# ZeroCrossingDetector.net
KiCad netlist of a schematic drawn in Altium Designer
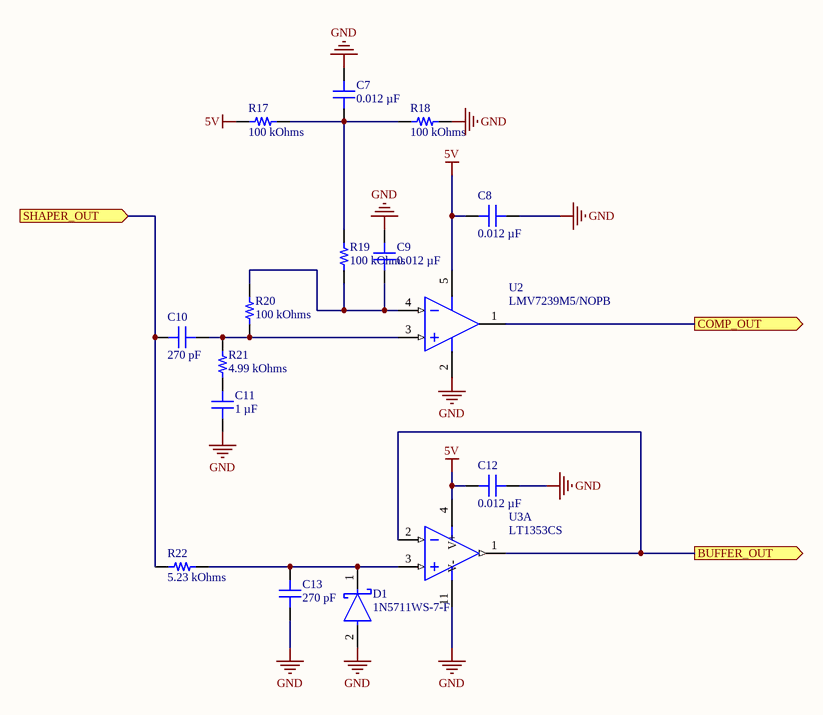
[diagram p0: ZeroCrossingDetector.SchDoc]

(export (version "E")
  (design (tool "Eeschema 10.0.6"))
  (components
    (comp (ref "C7")
      (value "0.012 µF")
      (footprint "CAP 0603_1608")
      (description "CAP CER 0.012UF 16V X7R 0603")
      (fields (field (name "PART NUMBER") "CC0603KRX7R7BB123") (field (name "MANUFACTURER") "Yageo"))
      (libsource (lib "CAL") (part "Capacitor"))
    )
    (comp (ref "C8")
      (value "0.012 µF")
      (footprint "CAP 0603_1608")
      (description "CAP CER 0.012UF 16V X7R 0603")
      (fields (field (name "PART NUMBER") "CC0603KRX7R7BB123") (field (name "MANUFACTURER") "Yageo"))
      (libsource (lib "CAL") (part "Capacitor"))
    )
    (comp (ref "C9")
      (value "0.012 µF")
      (footprint "CAP 0603_1608")
      (description "CAP CER 0.012UF 16V X7R 0603")
      (fields (field (name "PART NUMBER") "CC0603KRX7R7BB123") (field (name "MANUFACTURER") "Yageo"))
      (libsource (lib "CAL") (part "Capacitor"))
    )
    (comp (ref "C10")
      (value "270 pF")
      (footprint "CAP 0603_1608")
      (description "CAP CER 270 PF 16V C0G 0603")
      (fields
        (field (name "PART NUMBER") "VJ0603D271JXJQJHT")
        (field (name "MANUFACTURER") "Vishay Vitramon")
      )
      (libsource (lib "CAL") (part "Capacitor"))
    )
    (comp (ref "C11")
      (value "1 µF")
      (footprint "CAP 0603_1608")
      (description "CAP CER 1UF 16V X5R 0603")
      (fields (field (name "PART NUMBER") "CC0603KRX5R7BB105") (field (name "MANUFACTURER") "Yageo"))
      (libsource (lib "CAL") (part "Capacitor"))
    )
    (comp (ref "C12")
      (value "0.012 µF")
      (footprint "CAP 0603_1608")
      (description "CAP CER 0.012UF 16V X7R 0603")
      (fields (field (name "PART NUMBER") "CC0603KRX7R7BB123") (field (name "MANUFACTURER") "Yageo"))
      (libsource (lib "CAL") (part "Capacitor"))
    )
    (comp (ref "C13")
      (value "270 pF")
      (footprint "CAP 0603_1608")
      (description "CAP CER 270 PF 16V C0G 0603")
      (fields
        (field (name "PART NUMBER") "VJ0603D271JXJQJHT")
        (field (name "MANUFACTURER") "Vishay Vitramon")
      )
      (libsource (lib "CAL") (part "Capacitor"))
    )
    (comp (ref "D1")
      (value "1N5711WS-7-F")
      (footprint "FP-SOD323-MFG")
      (description "DIODE SCHOTTKY 70V 150MW SOD323")
      (fields
        (field (name "OCTOPART") "https://octopart.com/1n5711ws-7-f-diodes+inc.-323167")
        (field (name "MANUFACTURER") "Diodes Inc")
      )
      (libsource (lib "Altium Content Vault") (part "1d6ec82d83fb6aee721767c19dac4b9"))
    )
    (comp (ref "R17")
      (value "100 kOhms")
      (footprint "RES 0603_1608")
      (description "RCC0603 100 100K 1% ET1 E3")
      (fields (field (name "PART NUMBER") "RCC0603100KFKEA") (field (name "MANUFACTURER") "Vishay Dale"))
      (libsource (lib "CAL") (part "Resistor"))
    )
    (comp (ref "R18")
      (value "100 kOhms")
      (footprint "RES 0603_1608")
      (description "RCC0603 100 100K 1% ET1 E3")
      (fields (field (name "PART NUMBER") "RCC0603100KFKEA") (field (name "MANUFACTURER") "Vishay Dale"))
      (libsource (lib "CAL") (part "Resistor"))
    )
    (comp (ref "R19")
      (value "100 kOhms")
      (footprint "RES 0603_1608")
      (description "RCC0603 100 100K 1% ET1 E3")
      (fields (field (name "PART NUMBER") "RCC0603100KFKEA") (field (name "MANUFACTURER") "Vishay Dale"))
      (libsource (lib "CAL") (part "Resistor"))
    )
    (comp (ref "R20")
      (value "100 kOhms")
      (footprint "RES 0603_1608")
      (description "RCC0603 100 100K 1% ET1 E3")
      (fields (field (name "PART NUMBER") "RCC0603100KFKEA") (field (name "MANUFACTURER") "Vishay Dale"))
      (libsource (lib "CAL") (part "Resistor"))
    )
    (comp (ref "R21")
      (value "4.99 kOhms")
      (footprint "RES 0603_1608")
      (description "PTN0603 10PPM 4.99K 0.1% S T1 E1")
      (fields
        (field (name "PART NUMBER") "PTN0603Y4991BST1")
        (field (name "MANUFACTURER") "Vishay Dale Thin Film")
      )
      (libsource (lib "CAL") (part "Resistor"))
    )
    (comp (ref "R22")
      (value "5.23 kOhms")
      (footprint "RES 0603_1608")
      (description "RES 5.23K OHM 0.1% 1/10W 0603")
      (fields (field (name "PART NUMBER") "TNPW06035K23BEEA") (field (name "MANUFACTURER") "Vishay Dale"))
      (libsource (lib "CAL") (part "Resistor"))
    )
    (comp (ref "U2")
      (value "LMV7239M5/NOPB")
      (footprint "DBV0005A_L")
      (fields (field (name "MANUFACTURER") "Texas Instruments"))
      (libsource (lib "Altium Content Vault") (part "AN-COMP-LMV7235-5"))
    )
    (comp (ref "U3")
      (value "LT1353CS")
      (footprint "LT-S-14_N")
      (fields
        (field (name "LINEAR TECHNOLOGY PART NUMBER") "LT1353")
        (field (name "MANUFACTURER") "Linear Technology")
      )
      (libsource (lib "Altium Content Vault") (part "LT-135X-146X-181X-14"))
    )
  )
  (nets
    (net (code "1") (name "/BUFFER_OUT") (class "Default")
      (node (ref "U3") (pin "1") (pinfunction "OUT_A_1") (pintype "output"))
      (node (ref "U3") (pin "2") (pinfunction "-IN_A_2") (pintype "input"))
    )
    (net (code "2") (name "/COMP_OUT") (class "Default")
      (node (ref "U2") (pin "1") (pinfunction "VOUT_1") (pintype "open_collector"))
    )
    (net (code "3") (name "/SHAPER_OUT") (class "Default")
      (node (ref "C10") (pin "1") (pinfunction "1_1") (pintype "passive"))
      (node (ref "R22") (pin "1") (pinfunction "1_1") (pintype "passive"))
    )
    (net (code "4") (name "5V") (class "Default")
      (node (ref "C12") (pin "2") (pinfunction "2_2") (pintype "passive"))
      (node (ref "C8") (pin "2") (pinfunction "2_2") (pintype "passive"))
      (node (ref "R17") (pin "1") (pinfunction "1_1") (pintype "passive"))
      (node (ref "U2") (pin "5") (pinfunction "V+_5") (pintype "power_in"))
      (node (ref "U3") (pin "4") (pinfunction "V+_4") (pintype "power_in"))
    )
    (net (code "5") (name "GND") (class "Default")
      (node (ref "C11") (pin "1") (pinfunction "1_1") (pintype "passive"))
      (node (ref "C12") (pin "1") (pinfunction "1_1") (pintype "passive"))
      (node (ref "C13") (pin "1") (pinfunction "1_1") (pintype "passive"))
      (node (ref "C7") (pin "1") (pinfunction "1_1") (pintype "passive"))
      (node (ref "C8") (pin "1") (pinfunction "1_1") (pintype "passive"))
      (node (ref "C9") (pin "1") (pinfunction "1_1") (pintype "passive"))
      (node (ref "D1") (pin "2") (pinfunction "A_2") (pintype "passive"))
      (node (ref "R18") (pin "2") (pinfunction "2_2") (pintype "passive"))
      (node (ref "U2") (pin "2") (pinfunction "V-_2") (pintype "power_in"))
      (node (ref "U3") (pin "11") (pinfunction "V-_11") (pintype "power_in"))
    )
    (net (code "6") (name "Net-(C7-Pad2)") (class "Default")
      (node (ref "C7") (pin "2") (pinfunction "2_2") (pintype "passive"))
      (node (ref "R17") (pin "2") (pinfunction "2_2") (pintype "passive"))
      (node (ref "R18") (pin "1") (pinfunction "1_1") (pintype "passive"))
      (node (ref "R19") (pin "2") (pinfunction "2_2") (pintype "passive"))
    )
    (net (code "7") (name "Net-(D1-C)") (class "Default")
      (node (ref "C13") (pin "2") (pinfunction "2_2") (pintype "passive"))
      (node (ref "D1") (pin "1") (pinfunction "C_1") (pintype "passive"))
      (node (ref "R22") (pin "2") (pinfunction "2_2") (pintype "passive"))
      (node (ref "U3") (pin "3") (pinfunction "+IN_A_3") (pintype "input"))
    )
    (net (code "8") (name "Net-(U2-IN+)") (class "Default")
      (node (ref "C10") (pin "2") (pinfunction "2_2") (pintype "passive"))
      (node (ref "R20") (pin "1") (pinfunction "1_1") (pintype "passive"))
      (node (ref "R21") (pin "2") (pinfunction "2_2") (pintype "passive"))
      (node (ref "U2") (pin "3") (pinfunction "IN+_3") (pintype "input"))
    )
    (net (code "9") (name "Net-(U2-IN-)") (class "Default")
      (node (ref "C9") (pin "2") (pinfunction "2_2") (pintype "passive"))
      (node (ref "R19") (pin "1") (pinfunction "1_1") (pintype "passive"))
      (node (ref "R20") (pin "2") (pinfunction "2_2") (pintype "passive"))
      (node (ref "U2") (pin "4") (pinfunction "IN-_4") (pintype "input"))
    )
    (net (code "10") (name "unconnected-(C11-Pad2)") (class "Default")
      (node (ref "C11") (pin "2") (pinfunction "2_2") (pintype "passive"))
    )
    (net (code "11") (name "unconnected-(R21-Pad1)") (class "Default")
      (node (ref "R21") (pin "1") (pinfunction "1_1") (pintype "passive"))
    )
  )
)
